# sc.net
KiCad netlist of a schematic drawn in EAGLE
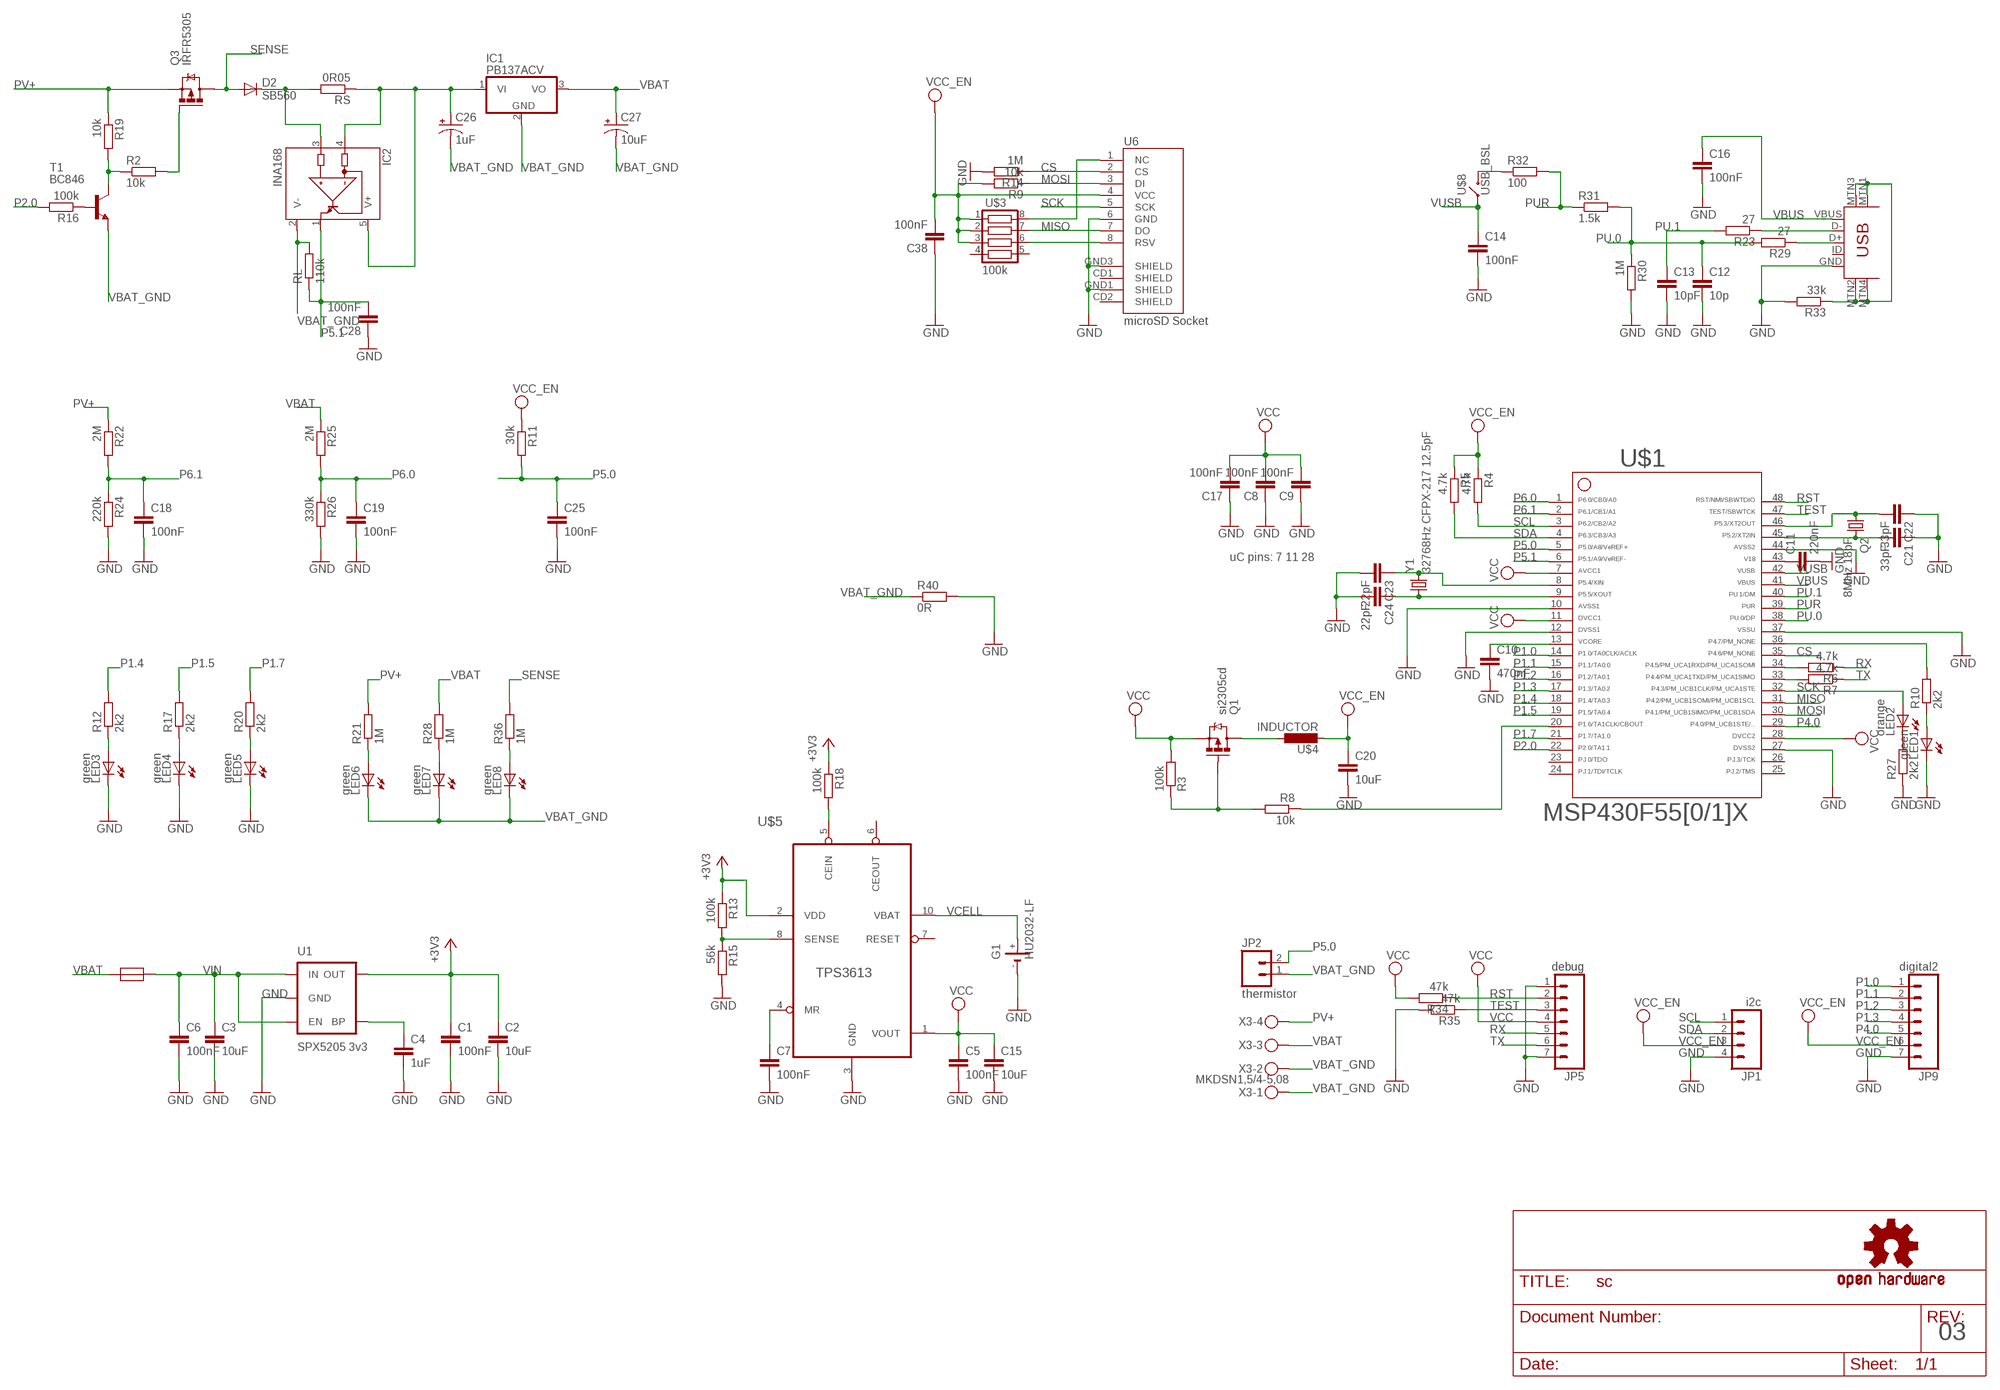
[diagram p0: schematic, sheet 1]

(export (version "E")
  (design (tool "Eeschema 10.0.6"))
  (components
    (comp (ref "C1")
      (value "100nF")
      (footprint "eagle-import:C0805")
      (libsource (lib "eagle-import") (part "C-EUC0805"))
    )
    (comp (ref "C2")
      (value "10uF")
      (footprint "eagle-import:C1206")
      (libsource (lib "eagle-import") (part "C-EUC1206"))
    )
    (comp (ref "C3")
      (value "10uF")
      (footprint "eagle-import:C1206")
      (libsource (lib "eagle-import") (part "C-EUC1206"))
    )
    (comp (ref "C4")
      (value "1uF")
      (footprint "eagle-import:C0805")
      (libsource (lib "eagle-import") (part "C-EUC0805"))
    )
    (comp (ref "C5")
      (value "100nF")
      (footprint "eagle-import:C0805")
      (libsource (lib "eagle-import") (part "C-EUC0805"))
    )
    (comp (ref "C6")
      (value "100nF")
      (footprint "eagle-import:C0805")
      (libsource (lib "eagle-import") (part "C-EUC0805"))
    )
    (comp (ref "C7")
      (value "100nF")
      (footprint "eagle-import:C0805")
      (libsource (lib "eagle-import") (part "C-EUC0805"))
    )
    (comp (ref "C8")
      (value "100nF")
      (footprint "eagle-import:C0805")
      (libsource (lib "eagle-import") (part "C-EUC0805"))
    )
    (comp (ref "C9")
      (value "100nF")
      (footprint "eagle-import:C0805")
      (libsource (lib "eagle-import") (part "C-EUC0805"))
    )
    (comp (ref "C10")
      (value "470nF")
      (footprint "eagle-import:C0805")
      (libsource (lib "eagle-import") (part "C-EUC0805"))
    )
    (comp (ref "C11")
      (value "220nF")
      (footprint "eagle-import:C0805")
      (libsource (lib "eagle-import") (part "C-EUC0805"))
    )
    (comp (ref "C12")
      (value "10p")
      (footprint "eagle-import:C0805")
      (libsource (lib "eagle-import") (part "C-EUC0805"))
    )
    (comp (ref "C13")
      (value "10pF")
      (footprint "eagle-import:C0805")
      (libsource (lib "eagle-import") (part "C-EUC0805"))
    )
    (comp (ref "C14")
      (value "100nF")
      (footprint "eagle-import:C0805")
      (libsource (lib "eagle-import") (part "C-EUC0805"))
    )
    (comp (ref "C15")
      (value "10uF")
      (footprint "eagle-import:C1206")
      (libsource (lib "eagle-import") (part "C-EUC1206"))
    )
    (comp (ref "C16")
      (value "100nF")
      (footprint "eagle-import:C0805")
      (libsource (lib "eagle-import") (part "C-EUC0805"))
    )
    (comp (ref "C17")
      (value "100nF")
      (footprint "eagle-import:C0805")
      (libsource (lib "eagle-import") (part "C-EUC0805"))
    )
    (comp (ref "C18")
      (value "100nF")
      (footprint "eagle-import:C0805")
      (libsource (lib "eagle-import") (part "C-EUC0805"))
    )
    (comp (ref "C19")
      (value "100nF")
      (footprint "eagle-import:C0805")
      (libsource (lib "eagle-import") (part "C-EUC0805"))
    )
    (comp (ref "C20")
      (value "10uF")
      (footprint "eagle-import:C1206")
      (libsource (lib "eagle-import") (part "C-EUC1206"))
    )
    (comp (ref "C21")
      (value "33pF")
      (footprint "eagle-import:C0805")
      (libsource (lib "eagle-import") (part "C-EUC0805"))
    )
    (comp (ref "C22")
      (value "33pF")
      (footprint "eagle-import:C0805")
      (libsource (lib "eagle-import") (part "C-EUC0805"))
    )
    (comp (ref "C23")
      (value "22pF")
      (footprint "eagle-import:C0805")
      (libsource (lib "eagle-import") (part "C-EUC0805"))
    )
    (comp (ref "C24")
      (value "22pF")
      (footprint "eagle-import:C0805")
      (libsource (lib "eagle-import") (part "C-EUC0805"))
    )
    (comp (ref "C25")
      (value "100nF")
      (footprint "eagle-import:C0805")
      (libsource (lib "eagle-import") (part "C-EUC0805"))
    )
    (comp (ref "C26")
      (value "1uF")
      (footprint "eagle-import:PANASONIC_D")
      (libsource (lib "eagle-import") (part "CAP_POLD"))
    )
    (comp (ref "C27")
      (value "10uF")
      (footprint "eagle-import:PANASONIC_D")
      (libsource (lib "eagle-import") (part "CAP_POLD"))
    )
    (comp (ref "C28")
      (value "100nF")
      (footprint "eagle-import:C0805")
      (libsource (lib "eagle-import") (part "C-EUC0805"))
    )
    (comp (ref "C38")
      (value "100nF")
      (footprint "eagle-import:C0805")
      (libsource (lib "eagle-import") (part "C-EUC0805"))
    )
    (comp (ref "D2")
      (value "SB560")
      (footprint "eagle-import:C1702-05")
      (libsource (lib "eagle-import") (part "DIODE-C1702-05"))
    )
    (comp (ref "G1")
      (value "HU2032-LF")
      (footprint "eagle-import:HU2032-LF")
      (libsource (lib "eagle-import") (part "HU2032-LF"))
    )
    (comp (ref "IC1")
      (value "PB137ACV")
      (footprint "eagle-import:TO220V")
      (libsource (lib "eagle-import") (part "78TV12"))
    )
    (comp (ref "IC2")
      (value "INA168")
      (footprint "eagle-import:SOT23-5")
      (fields (field (name "MF") "TEXAS INSTRUMENTS") (field (name "MPN") "INA168NA/250"))
      (libsource (lib "eagle-import") (part "INA168"))
    )
    (comp (ref "JP1")
      (value "i2c")
      (footprint "eagle-import:1X04")
      (libsource (lib "eagle-import") (part "M04PTH"))
    )
    (comp (ref "JP2")
      (value "thermistor")
      (footprint "eagle-import:1X02")
      (libsource (lib "eagle-import") (part "M02PTH"))
    )
    (comp (ref "JP5")
      (value "debug")
      (footprint "eagle-import:1X07")
      (libsource (lib "eagle-import") (part "M07"))
    )
    (comp (ref "JP9")
      (value "digital2")
      (footprint "eagle-import:1X07")
      (libsource (lib "eagle-import") (part "M07"))
    )
    (comp (ref "LED1")
      (value "green")
      (footprint "eagle-import:CHIP-LED0805")
      (libsource (lib "eagle-import") (part "LEDCHIP-LED0805"))
    )
    (comp (ref "LED2")
      (value "orange")
      (footprint "eagle-import:CHIP-LED0805")
      (libsource (lib "eagle-import") (part "LEDCHIP-LED0805"))
    )
    (comp (ref "LED3")
      (value "green")
      (footprint "eagle-import:CHIP-LED0805")
      (libsource (lib "eagle-import") (part "LEDCHIP-LED0805"))
    )
    (comp (ref "LED4")
      (value "green")
      (footprint "eagle-import:CHIP-LED0805")
      (libsource (lib "eagle-import") (part "LEDCHIP-LED0805"))
    )
    (comp (ref "LED5")
      (value "green")
      (footprint "eagle-import:CHIP-LED0805")
      (libsource (lib "eagle-import") (part "LEDCHIP-LED0805"))
    )
    (comp (ref "LED6")
      (value "green")
      (footprint "eagle-import:CHIP-LED0805")
      (libsource (lib "eagle-import") (part "LEDCHIP-LED0805"))
    )
    (comp (ref "LED7")
      (value "green")
      (footprint "eagle-import:CHIP-LED0805")
      (libsource (lib "eagle-import") (part "LEDCHIP-LED0805"))
    )
    (comp (ref "LED8")
      (value "green")
      (footprint "eagle-import:CHIP-LED0805")
      (libsource (lib "eagle-import") (part "LEDCHIP-LED0805"))
    )
    (comp (ref "Q1")
      (value "si2305cd")
      (footprint "eagle-import:SOT23-3_POWER")
      (libsource (lib "eagle-import") (part "MOSFET-PCHANNELSMD_POWER"))
    )
    (comp (ref "Q2")
      (value "8MHz 18pF")
      (footprint "eagle-import:CRYSTAL_5X3.2")
      (libsource (lib "eagle-import") (part "CRYTAL"))
    )
    (comp (ref "Q3")
      (value "IRFR5305")
      (footprint "eagle-import:D-PAK_TO252AA")
      (libsource (lib "eagle-import") (part "IRF?5305R"))
    )
    (comp (ref "R2")
      (value "10k")
      (footprint "eagle-import:R0805W")
      (libsource (lib "eagle-import") (part "R-EU_R0805W"))
    )
    (comp (ref "R3")
      (value "100k")
      (footprint "eagle-import:R0805W")
      (libsource (lib "eagle-import") (part "R-EU_R0805W"))
    )
    (comp (ref "R4")
      (value "4.7k")
      (footprint "eagle-import:R0805W")
      (libsource (lib "eagle-import") (part "R-EU_R0805W"))
    )
    (comp (ref "R5")
      (value "4.7k")
      (footprint "eagle-import:R0805W")
      (libsource (lib "eagle-import") (part "R-EU_R0805W"))
    )
    (comp (ref "R6")
      (value "4.7k")
      (footprint "eagle-import:R0805W")
      (libsource (lib "eagle-import") (part "R-EU_R0805W"))
    )
    (comp (ref "R7")
      (value "4.7k")
      (footprint "eagle-import:R0805W")
      (libsource (lib "eagle-import") (part "R-EU_R0805W"))
    )
    (comp (ref "R8")
      (value "10k")
      (footprint "eagle-import:R0805W")
      (libsource (lib "eagle-import") (part "R-EU_R0805W"))
    )
    (comp (ref "R9")
      (value "10k")
      (footprint "eagle-import:R0805W")
      (libsource (lib "eagle-import") (part "R-EU_R0805W"))
    )
    (comp (ref "R10")
      (value "2k2")
      (footprint "eagle-import:R0805W")
      (libsource (lib "eagle-import") (part "R-EU_R0805W"))
    )
    (comp (ref "R11")
      (value "30k")
      (footprint "eagle-import:R0805W")
      (libsource (lib "eagle-import") (part "R-EU_R0805W"))
    )
    (comp (ref "R12")
      (value "2k2")
      (footprint "eagle-import:R0805W")
      (libsource (lib "eagle-import") (part "R-EU_R0805W"))
    )
    (comp (ref "R13")
      (value "100k")
      (footprint "eagle-import:R0805W")
      (libsource (lib "eagle-import") (part "R-EU_R0805W"))
    )
    (comp (ref "R14")
      (value "1M")
      (footprint "eagle-import:R0805W")
      (libsource (lib "eagle-import") (part "R-EU_R0805W"))
    )
    (comp (ref "R15")
      (value "56k")
      (footprint "eagle-import:R0805W")
      (libsource (lib "eagle-import") (part "R-EU_R0805W"))
    )
    (comp (ref "R16")
      (value "100k")
      (footprint "eagle-import:R0805W")
      (libsource (lib "eagle-import") (part "R-EU_R0805W"))
    )
    (comp (ref "R17")
      (value "2k2")
      (footprint "eagle-import:R0805W")
      (libsource (lib "eagle-import") (part "R-EU_R0805W"))
    )
    (comp (ref "R18")
      (value "100k")
      (footprint "eagle-import:R0805W")
      (libsource (lib "eagle-import") (part "R-EU_R0805W"))
    )
    (comp (ref "R19")
      (value "10k")
      (footprint "eagle-import:R0805W")
      (libsource (lib "eagle-import") (part "R-EU_R0805W"))
    )
    (comp (ref "R20")
      (value "2k2")
      (footprint "eagle-import:R0805W")
      (libsource (lib "eagle-import") (part "R-EU_R0805W"))
    )
    (comp (ref "R21")
      (value "1M")
      (footprint "eagle-import:R0805W")
      (libsource (lib "eagle-import") (part "R-EU_R0805W"))
    )
    (comp (ref "R22")
      (value "2M")
      (footprint "eagle-import:R0805W")
      (libsource (lib "eagle-import") (part "R-EU_R0805W"))
    )
    (comp (ref "R23")
      (value "27")
      (footprint "eagle-import:R0805W")
      (libsource (lib "eagle-import") (part "R-EU_R0805W"))
    )
    (comp (ref "R24")
      (value "220k")
      (footprint "eagle-import:R0805W")
      (libsource (lib "eagle-import") (part "R-EU_R0805W"))
    )
    (comp (ref "R25")
      (value "2M")
      (footprint "eagle-import:R0805W")
      (libsource (lib "eagle-import") (part "R-EU_R0805W"))
    )
    (comp (ref "R26")
      (value "330k")
      (footprint "eagle-import:R0805W")
      (libsource (lib "eagle-import") (part "R-EU_R0805W"))
    )
    (comp (ref "R27")
      (value "2k2")
      (footprint "eagle-import:R0805W")
      (libsource (lib "eagle-import") (part "R-EU_R0805W"))
    )
    (comp (ref "R28")
      (value "1M")
      (footprint "eagle-import:R0805W")
      (libsource (lib "eagle-import") (part "R-EU_R0805W"))
    )
    (comp (ref "R29")
      (value "27")
      (footprint "eagle-import:R0805W")
      (libsource (lib "eagle-import") (part "R-EU_R0805W"))
    )
    (comp (ref "R30")
      (value "1M")
      (footprint "eagle-import:R0805W")
      (libsource (lib "eagle-import") (part "R-EU_R0805W"))
    )
    (comp (ref "R31")
      (value "1.5k")
      (footprint "eagle-import:R0805W")
      (libsource (lib "eagle-import") (part "R-EU_R0805W"))
    )
    (comp (ref "R32")
      (value "100")
      (footprint "eagle-import:R0805W")
      (libsource (lib "eagle-import") (part "R-EU_R0805W"))
    )
    (comp (ref "R33")
      (value "33k")
      (footprint "eagle-import:R0805W")
      (libsource (lib "eagle-import") (part "R-EU_R0805W"))
    )
    (comp (ref "R34")
      (value "47k")
      (footprint "eagle-import:R0805W")
      (libsource (lib "eagle-import") (part "R-EU_R0805W"))
    )
    (comp (ref "R35")
      (value "47k")
      (footprint "eagle-import:R0805W")
      (libsource (lib "eagle-import") (part "R-EU_R0805W"))
    )
    (comp (ref "R36")
      (value "1M")
      (footprint "eagle-import:R0805W")
      (libsource (lib "eagle-import") (part "R-EU_R0805W"))
    )
    (comp (ref "R40")
      (value "0R")
      (footprint "eagle-import:R0805W")
      (libsource (lib "eagle-import") (part "R-EU_R0805W"))
    )
    (comp (ref "RL")
      (value "110k")
      (footprint "eagle-import:R0805W")
      (libsource (lib "eagle-import") (part "R-EU_R0805W"))
    )
    (comp (ref "RS")
      (value "0R05")
      (footprint "eagle-import:TO220ACS")
      (libsource (lib "eagle-import") (part "R-EU_TO220_V"))
    )
    (comp (ref "T1")
      (value "BC846")
      (footprint "eagle-import:SOT23")
      (libsource (lib "eagle-import") (part "BC846"))
    )
    (comp (ref "U$1")
      (value "F55[0/1]X---PT48")
      (footprint "eagle-import:PT48")
      (libsource (lib "eagle-import") (part "F55[0/1]X---PT48"))
    )
    (comp (ref "U$2")
      (value "RESETTABLE")
      (footprint "eagle-import:1210")
      (libsource (lib "eagle-import") (part "RESETTABLE"))
    )
    (comp (ref "U$3")
      (value "100k")
      (footprint "eagle-import:YC164")
      (libsource (lib "eagle-import") (part "RES_ARR"))
    )
    (comp (ref "U$4")
      (value "INDUCTOR")
      (footprint "eagle-import:L0805W")
      (libsource (lib "eagle-import") (part "INDUCTOR"))
    )
    (comp (ref "U$5")
      (value "TPS3613")
      (footprint "eagle-import:MSOP_10P")
      (libsource (lib "eagle-import") (part "TPS3613"))
    )
    (comp (ref "U$6")
      (value "USB-MINIB-5PIN")
      (footprint "eagle-import:USB-MINIB")
      (libsource (lib "eagle-import") (part "USB-MINIB-5PIN"))
    )
    (comp (ref "U$7")
      (value "OSHW-LOGOM")
      (footprint "eagle-import:OSHW-LOGO-M")
      (libsource (lib "eagle-import") (part "OSHW-LOGOM"))
    )
    (comp (ref "U$8")
      (value "USB_BSL")
      (footprint "eagle-import:6X3.5_TACTILE_SW")
      (libsource (lib "eagle-import") (part "TACT_SW"))
    )
    (comp (ref "U1")
      (value "SPX5205 3v3")
      (footprint "eagle-import:SOT23-5")
      (libsource (lib "eagle-import") (part "V_REG_LDOSMD"))
    )
    (comp (ref "U6")
      (value "microSD Socket")
      (footprint "eagle-import:MICRO-SD-SOCKET-PP")
      (libsource (lib "eagle-import") (part "USD-SOCKETNEW"))
    )
    (comp (ref "X3")
      (value "MKDSN1,5/4-5,08")
      (footprint "eagle-import:MKDSN1,5_4-5,08")
      (fields (field (name "MPN") "SMKDSN1,5/4-5,08"))
      (libsource (lib "eagle-import") (part "MKDSN1,5/4-5,08"))
    )
    (comp (ref "Y1")
      (value "32768Hz CFPX-217 12.5pF")
      (footprint "eagle-import:CRYSTAL-SMD-3.2X1.5")
      (libsource (lib "eagle-import") (part "CRYSTAL3.2X1.5"))
    )
  )
  (nets
    (net (code "1") (name "+3V3") (class "Default")
      (node (ref "C1") (pin "1") (pinfunction "1_1") (pintype "passive"))
      (node (ref "C2") (pin "1") (pinfunction "1_1") (pintype "passive"))
      (node (ref "R13") (pin "1") (pinfunction "1_1") (pintype "passive"))
      (node (ref "R18") (pin "1") (pinfunction "1_1") (pintype "passive"))
      (node (ref "U$5") (pin "2") (pinfunction "VDD_2") (pintype "power_in"))
      (node (ref "U1") (pin "5") (pinfunction "OUT_5") (pintype "passive"))
    )
    (net (code "2") (name "/CS") (class "Default")
      (node (ref "R14") (pin "1") (pinfunction "1_1") (pintype "passive"))
      (node (ref "U$1") (pin "35") (pinfunction "35_35") (pintype "bidirectional"))
      (node (ref "U6") (pin "2") (pinfunction "CS_2") (pintype "bidirectional"))
    )
    (net (code "3") (name "/MISO") (class "Default")
      (node (ref "U$1") (pin "31") (pinfunction "31_31") (pintype "bidirectional"))
      (node (ref "U$3") (pin "7") (pinfunction "7_7") (pintype "passive"))
      (node (ref "U6") (pin "7") (pinfunction "DO_7") (pintype "bidirectional"))
    )
    (net (code "4") (name "/MOSI") (class "Default")
      (node (ref "R9") (pin "1") (pinfunction "1_1") (pintype "passive"))
      (node (ref "U$1") (pin "30") (pinfunction "30_30") (pintype "bidirectional"))
      (node (ref "U6") (pin "3") (pinfunction "DI_3") (pintype "bidirectional"))
    )
    (net (code "5") (name "/P1.0") (class "Default")
      (node (ref "JP9") (pin "1") (pinfunction "1_1") (pintype "passive"))
      (node (ref "U$1") (pin "14") (pinfunction "14_14") (pintype "bidirectional"))
    )
    (net (code "6") (name "/P1.1") (class "Default")
      (node (ref "JP9") (pin "2") (pinfunction "2_2") (pintype "passive"))
      (node (ref "U$1") (pin "15") (pinfunction "15_15") (pintype "bidirectional"))
    )
    (net (code "7") (name "/P1.2") (class "Default")
      (node (ref "JP9") (pin "3") (pinfunction "3_3") (pintype "passive"))
      (node (ref "U$1") (pin "16") (pinfunction "16_16") (pintype "bidirectional"))
    )
    (net (code "8") (name "/P1.3") (class "Default")
      (node (ref "JP9") (pin "4") (pinfunction "4_4") (pintype "passive"))
      (node (ref "U$1") (pin "17") (pinfunction "17_17") (pintype "bidirectional"))
    )
    (net (code "9") (name "/P1.4") (class "Default")
      (node (ref "R12") (pin "2") (pinfunction "2_2") (pintype "passive"))
      (node (ref "U$1") (pin "18") (pinfunction "18_18") (pintype "bidirectional"))
    )
    (net (code "10") (name "/P1.5") (class "Default")
      (node (ref "R17") (pin "2") (pinfunction "2_2") (pintype "passive"))
      (node (ref "U$1") (pin "19") (pinfunction "19_19") (pintype "bidirectional"))
    )
    (net (code "11") (name "/P1.7") (class "Default")
      (node (ref "R20") (pin "2") (pinfunction "2_2") (pintype "passive"))
      (node (ref "U$1") (pin "21") (pinfunction "21_21") (pintype "bidirectional"))
    )
    (net (code "12") (name "/P2.0") (class "Default")
      (node (ref "R16") (pin "2") (pinfunction "2_2") (pintype "passive"))
      (node (ref "U$1") (pin "22") (pinfunction "22_22") (pintype "bidirectional"))
    )
    (net (code "13") (name "/P4.0") (class "Default")
      (node (ref "JP9") (pin "5") (pinfunction "5_5") (pintype "passive"))
      (node (ref "U$1") (pin "29") (pinfunction "29_29") (pintype "bidirectional"))
    )
    (net (code "14") (name "/P5.0") (class "Default")
      (node (ref "C25") (pin "1") (pinfunction "1_1") (pintype "passive"))
      (node (ref "JP2") (pin "2") (pinfunction "2_2") (pintype "passive"))
      (node (ref "R11") (pin "2") (pinfunction "2_2") (pintype "passive"))
      (node (ref "U$1") (pin "5") (pinfunction "5_5") (pintype "bidirectional"))
    )
    (net (code "15") (name "/P5.1") (class "Default")
      (node (ref "C28") (pin "2") (pinfunction "2_2") (pintype "passive"))
      (node (ref "IC2") (pin "1") (pinfunction "OUT_1") (pintype "output"))
      (node (ref "RL") (pin "1") (pinfunction "1_1") (pintype "passive"))
      (node (ref "U$1") (pin "6") (pinfunction "6_6") (pintype "bidirectional"))
    )
    (net (code "16") (name "/P6.0") (class "Default")
      (node (ref "C19") (pin "1") (pinfunction "1_1") (pintype "passive"))
      (node (ref "R25") (pin "2") (pinfunction "2_2") (pintype "passive"))
      (node (ref "R26") (pin "1") (pinfunction "1_1") (pintype "passive"))
      (node (ref "U$1") (pin "1") (pinfunction "1_1") (pintype "bidirectional"))
    )
    (net (code "17") (name "/P6.1") (class "Default")
      (node (ref "C18") (pin "1") (pinfunction "1_1") (pintype "passive"))
      (node (ref "R22") (pin "2") (pinfunction "2_2") (pintype "passive"))
      (node (ref "R24") (pin "1") (pinfunction "1_1") (pintype "passive"))
      (node (ref "U$1") (pin "2") (pinfunction "2_2") (pintype "bidirectional"))
    )
    (net (code "18") (name "/PU.0") (class "Default")
      (node (ref "C12") (pin "1") (pinfunction "1_1") (pintype "passive"))
      (node (ref "R29") (pin "2") (pinfunction "2_2") (pintype "passive"))
      (node (ref "R30") (pin "1") (pinfunction "1_1") (pintype "passive"))
      (node (ref "R31") (pin "2") (pinfunction "2_2") (pintype "passive"))
      (node (ref "U$1") (pin "38") (pinfunction "38_38") (pintype "bidirectional"))
    )
    (net (code "19") (name "/PU.1") (class "Default")
      (node (ref "C13") (pin "1") (pinfunction "1_1") (pintype "passive"))
      (node (ref "R23") (pin "2") (pinfunction "2_2") (pintype "passive"))
      (node (ref "U$1") (pin "40") (pinfunction "40_40") (pintype "bidirectional"))
    )
    (net (code "20") (name "/PUR") (class "Default")
      (node (ref "R31") (pin "1") (pinfunction "1_1") (pintype "passive"))
      (node (ref "R32") (pin "2") (pinfunction "2_2") (pintype "passive"))
      (node (ref "U$1") (pin "39") (pinfunction "39_39") (pintype "bidirectional"))
    )
    (net (code "21") (name "/PV+") (class "Default")
      (node (ref "Q3") (pin "3") (pinfunction "S_3") (pintype "passive"))
      (node (ref "R19") (pin "1") (pinfunction "1_1") (pintype "passive"))
      (node (ref "R21") (pin "2") (pinfunction "2_2") (pintype "passive"))
      (node (ref "R22") (pin "1") (pinfunction "1_1") (pintype "passive"))
      (node (ref "X3") (pin "4") (pinfunction "KL_4") (pintype "passive"))
    )
    (net (code "22") (name "/RST") (class "Default")
      (node (ref "JP5") (pin "2") (pinfunction "2_2") (pintype "passive"))
      (node (ref "R34") (pin "1") (pinfunction "1_1") (pintype "passive"))
      (node (ref "U$1") (pin "48") (pinfunction "48_48") (pintype "bidirectional"))
    )
    (net (code "23") (name "/RX") (class "Default")
      (node (ref "JP5") (pin "5") (pinfunction "5_5") (pintype "passive"))
      (node (ref "R6") (pin "1") (pinfunction "1_1") (pintype "passive"))
    )
    (net (code "24") (name "/SCK") (class "Default")
      (node (ref "LED2") (pin "A") (pinfunction "A_A") (pintype "passive"))
      (node (ref "U$1") (pin "32") (pinfunction "32_32") (pintype "bidirectional"))
      (node (ref "U6") (pin "5") (pinfunction "SCK_5") (pintype "bidirectional"))
    )
    (net (code "25") (name "/SCL") (class "Default")
      (node (ref "JP1") (pin "1") (pinfunction "1_1") (pintype "passive"))
      (node (ref "R4") (pin "2") (pinfunction "2_2") (pintype "passive"))
      (node (ref "U$1") (pin "3") (pinfunction "3_3") (pintype "bidirectional"))
    )
    (net (code "26") (name "/SDA") (class "Default")
      (node (ref "JP1") (pin "2") (pinfunction "2_2") (pintype "passive"))
      (node (ref "R5") (pin "2") (pinfunction "2_2") (pintype "passive"))
      (node (ref "U$1") (pin "4") (pinfunction "4_4") (pintype "bidirectional"))
    )
    (net (code "27") (name "/SENSE") (class "Default")
      (node (ref "D2") (pin "A") (pinfunction "A_A") (pintype "passive"))
      (node (ref "Q3") (pin "4") (pinfunction "D_4") (pintype "passive"))
      (node (ref "R36") (pin "2") (pinfunction "2_2") (pintype "passive"))
    )
    (net (code "28") (name "/TEST") (class "Default")
      (node (ref "JP5") (pin "3") (pinfunction "3_3") (pintype "passive"))
      (node (ref "R35") (pin "1") (pinfunction "1_1") (pintype "passive"))
      (node (ref "U$1") (pin "47") (pinfunction "47_47") (pintype "input"))
    )
    (net (code "29") (name "/TX") (class "Default")
      (node (ref "JP5") (pin "6") (pinfunction "6_6") (pintype "passive"))
      (node (ref "R7") (pin "1") (pinfunction "1_1") (pintype "passive"))
    )
    (net (code "30") (name "/VBAT") (class "Default")
      (node (ref "C27") (pin "+") (pinfunction "+_+") (pintype "passive"))
      (node (ref "IC1") (pin "3") (pinfunction "VO_3") (pintype "passive"))
      (node (ref "R25") (pin "1") (pinfunction "1_1") (pintype "passive"))
      (node (ref "R28") (pin "2") (pinfunction "2_2") (pintype "passive"))
      (node (ref "U$2") (pin "P$1") (pinfunction "P$1_P$1") (pintype "bidirectional"))
      (node (ref "X3") (pin "3") (pinfunction "KL_3") (pintype "passive"))
    )
    (net (code "31") (name "/VBAT_GND") (class "Default")
      (node (ref "C26") (pin "-") (pinfunction "-_-") (pintype "passive"))
      (node (ref "C27") (pin "-") (pinfunction "-_-") (pintype "passive"))
      (node (ref "IC1") (pin "2") (pinfunction "GND_2") (pintype "passive"))
      (node (ref "IC2") (pin "2") (pinfunction "V-_2") (pintype "power_in"))
      (node (ref "JP2") (pin "1") (pinfunction "1_1") (pintype "passive"))
      (node (ref "LED6") (pin "C") (pinfunction "C_C") (pintype "passive"))
      (node (ref "LED7") (pin "C") (pinfunction "C_C") (pintype "passive"))
      (node (ref "LED8") (pin "C") (pinfunction "C_C") (pintype "passive"))
      (node (ref "R40") (pin "1") (pinfunction "1_1") (pintype "passive"))
      (node (ref "RL") (pin "2") (pinfunction "2_2") (pintype "passive"))
      (node (ref "T1") (pin "2") (pinfunction "E_2") (pintype "passive"))
      (node (ref "X3") (pin "1") (pinfunction "KL_1") (pintype "passive"))
      (node (ref "X3") (pin "2") (pinfunction "KL_2") (pintype "passive"))
    )
    (net (code "32") (name "/VBUS") (class "Default")
      (node (ref "C16") (pin "1") (pinfunction "1_1") (pintype "passive"))
      (node (ref "U$1") (pin "41") (pinfunction "41_41") (pintype "power_in"))
      (node (ref "U$6") (pin "VBUS") (pinfunction "VBUS_VBUS") (pintype "bidirectional"))
    )
    (net (code "33") (name "/VCELL") (class "Default")
      (node (ref "G1") (pin "+") (pinfunction "+_+") (pintype "passive"))
      (node (ref "U$5") (pin "10") (pinfunction "VBAT_10") (pintype "power_in"))
    )
    (net (code "34") (name "/VIN") (class "Default")
      (node (ref "C3") (pin "1") (pinfunction "1_1") (pintype "passive"))
      (node (ref "C6") (pin "1") (pinfunction "1_1") (pintype "passive"))
      (node (ref "U$2") (pin "P$2") (pinfunction "P$2_P$2") (pintype "bidirectional"))
      (node (ref "U1") (pin "1") (pinfunction "IN_1") (pintype "input"))
      (node (ref "U1") (pin "3") (pinfunction "EN_3") (pintype "input"))
    )
    (net (code "35") (name "/VUSB") (class "Default")
      (node (ref "C14") (pin "1") (pinfunction "1_1") (pintype "passive"))
      (node (ref "U$1") (pin "42") (pinfunction "42_42") (pintype "power_in"))
      (node (ref "U$8") (pin "1") (pinfunction "1_1") (pintype "passive"))
    )
    (net (code "36") (name "GND") (class "Default")
      (node (ref "C1") (pin "2") (pinfunction "2_2") (pintype "passive"))
      (node (ref "C10") (pin "2") (pinfunction "2_2") (pintype "passive"))
      (node (ref "C11") (pin "2") (pinfunction "2_2") (pintype "passive"))
      (node (ref "C12") (pin "2") (pinfunction "2_2") (pintype "passive"))
      (node (ref "C13") (pin "2") (pinfunction "2_2") (pintype "passive"))
      (node (ref "C14") (pin "2") (pinfunction "2_2") (pintype "passive"))
      (node (ref "C15") (pin "2") (pinfunction "2_2") (pintype "passive"))
      (node (ref "C16") (pin "2") (pinfunction "2_2") (pintype "passive"))
      (node (ref "C17") (pin "1") (pinfunction "1_1") (pintype "passive"))
      (node (ref "C18") (pin "2") (pinfunction "2_2") (pintype "passive"))
      (node (ref "C19") (pin "2") (pinfunction "2_2") (pintype "passive"))
      (node (ref "C2") (pin "2") (pinfunction "2_2") (pintype "passive"))
      (node (ref "C20") (pin "2") (pinfunction "2_2") (pintype "passive"))
      (node (ref "C21") (pin "1") (pinfunction "1_1") (pintype "passive"))
      (node (ref "C22") (pin "1") (pinfunction "1_1") (pintype "passive"))
      (node (ref "C23") (pin "2") (pinfunction "2_2") (pintype "passive"))
      (node (ref "C24") (pin "2") (pinfunction "2_2") (pintype "passive"))
      (node (ref "C25") (pin "2") (pinfunction "2_2") (pintype "passive"))
      (node (ref "C28") (pin "1") (pinfunction "1_1") (pintype "passive"))
      (node (ref "C3") (pin "2") (pinfunction "2_2") (pintype "passive"))
      (node (ref "C38") (pin "1") (pinfunction "1_1") (pintype "passive"))
      (node (ref "C4") (pin "2") (pinfunction "2_2") (pintype "passive"))
      (node (ref "C5") (pin "2") (pinfunction "2_2") (pintype "passive"))
      (node (ref "C6") (pin "2") (pinfunction "2_2") (pintype "passive"))
      (node (ref "C7") (pin "2") (pinfunction "2_2") (pintype "passive"))
      (node (ref "C8") (pin "1") (pinfunction "1_1") (pintype "passive"))
      (node (ref "C9") (pin "1") (pinfunction "1_1") (pintype "passive"))
      (node (ref "G1") (pin "-") (pinfunction "-_-") (pintype "passive"))
      (node (ref "JP1") (pin "4") (pinfunction "4_4") (pintype "passive"))
      (node (ref "JP5") (pin "1") (pinfunction "1_1") (pintype "passive"))
      (node (ref "JP5") (pin "7") (pinfunction "7_7") (pintype "passive"))
      (node (ref "JP9") (pin "7") (pinfunction "7_7") (pintype "passive"))
      (node (ref "LED1") (pin "C") (pinfunction "C_C") (pintype "passive"))
      (node (ref "LED3") (pin "C") (pinfunction "C_C") (pintype "passive"))
      (node (ref "LED4") (pin "C") (pinfunction "C_C") (pintype "passive"))
      (node (ref "LED5") (pin "C") (pinfunction "C_C") (pintype "passive"))
      (node (ref "R14") (pin "2") (pinfunction "2_2") (pintype "passive"))
      (node (ref "R15") (pin "2") (pinfunction "2_2") (pintype "passive"))
      (node (ref "R24") (pin "2") (pinfunction "2_2") (pintype "passive"))
      (node (ref "R26") (pin "2") (pinfunction "2_2") (pintype "passive"))
      (node (ref "R27") (pin "1") (pinfunction "1_1") (pintype "passive"))
      (node (ref "R30") (pin "2") (pinfunction "2_2") (pintype "passive"))
      (node (ref "R33") (pin "2") (pinfunction "2_2") (pintype "passive"))
      (node (ref "R35") (pin "2") (pinfunction "2_2") (pintype "passive"))
      (node (ref "R40") (pin "2") (pinfunction "2_2") (pintype "passive"))
      (node (ref "U$1") (pin "10") (pinfunction "10_10") (pintype "power_in"))
      (node (ref "U$1") (pin "12") (pinfunction "12_12") (pintype "power_in"))
      (node (ref "U$1") (pin "27") (pinfunction "27_27") (pintype "power_in"))
      (node (ref "U$1") (pin "37") (pinfunction "37_37") (pintype "power_in"))
      (node (ref "U$1") (pin "44") (pinfunction "44_44") (pintype "power_in"))
      (node (ref "U$5") (pin "3") (pinfunction "GND_3") (pintype "passive"))
      (node (ref "U$6") (pin "GND") (pinfunction "GND_GND") (pintype "bidirectional"))
      (node (ref "U1") (pin "2") (pinfunction "GND_2") (pintype "input"))
      (node (ref "U6") (pin "6") (pinfunction "GND_6") (pintype "bidirectional"))
      (node (ref "U6") (pin "GND1") (pinfunction "SHIELD_GND1") (pintype "bidirectional"))
      (node (ref "U6") (pin "GND3") (pinfunction "SHIELD_GND3") (pintype "bidirectional"))
    )
    (net (code "37") (name "Net-(C10-Pad1)") (class "Default")
      (node (ref "C10") (pin "1") (pinfunction "1_1") (pintype "passive"))
      (node (ref "U$1") (pin "13") (pinfunction "13_13") (pintype "power_in"))
    )
    (net (code "38") (name "Net-(C11-Pad1)") (class "Default")
      (node (ref "C11") (pin "1") (pinfunction "1_1") (pintype "passive"))
      (node (ref "U$1") (pin "43") (pinfunction "43_43") (pintype "power_in"))
    )
    (net (code "39") (name "Net-(IC1-VI)") (class "Default")
      (node (ref "C26") (pin "+") (pinfunction "+_+") (pintype "passive"))
      (node (ref "IC1") (pin "1") (pinfunction "VI_1") (pintype "input"))
      (node (ref "IC2") (pin "4") (pinfunction "IN-_4") (pintype "input"))
      (node (ref "IC2") (pin "5") (pinfunction "V+_5") (pintype "power_in"))
      (node (ref "RS") (pin "A") (pinfunction "1_A") (pintype "passive"))
    )
    (net (code "40") (name "Net-(IC2-IN+)") (class "Default")
      (node (ref "D2") (pin "C") (pinfunction "C_C") (pintype "passive"))
      (node (ref "IC2") (pin "3") (pinfunction "IN+_3") (pintype "input"))
      (node (ref "RS") (pin "C") (pinfunction "2_C") (pintype "passive"))
    )
    (net (code "41") (name "Net-(LED1-PadA)") (class "Default")
      (node (ref "LED1") (pin "A") (pinfunction "A_A") (pintype "passive"))
      (node (ref "R10") (pin "1") (pinfunction "1_1") (pintype "passive"))
    )
    (net (code "42") (name "Net-(LED2-PadC)") (class "Default")
      (node (ref "LED2") (pin "C") (pinfunction "C_C") (pintype "passive"))
      (node (ref "R27") (pin "2") (pinfunction "2_2") (pintype "passive"))
    )
    (net (code "43") (name "Net-(LED3-PadA)") (class "Default")
      (node (ref "LED3") (pin "A") (pinfunction "A_A") (pintype "passive"))
      (node (ref "R12") (pin "1") (pinfunction "1_1") (pintype "passive"))
    )
    (net (code "44") (name "Net-(LED4-PadA)") (class "Default")
      (node (ref "LED4") (pin "A") (pinfunction "A_A") (pintype "passive"))
      (node (ref "R17") (pin "1") (pinfunction "1_1") (pintype "passive"))
    )
    (net (code "45") (name "Net-(LED5-PadA)") (class "Default")
      (node (ref "LED5") (pin "A") (pinfunction "A_A") (pintype "passive"))
      (node (ref "R20") (pin "1") (pinfunction "1_1") (pintype "passive"))
    )
    (net (code "46") (name "Net-(LED6-PadA)") (class "Default")
      (node (ref "LED6") (pin "A") (pinfunction "A_A") (pintype "passive"))
      (node (ref "R21") (pin "1") (pinfunction "1_1") (pintype "passive"))
    )
    (net (code "47") (name "Net-(LED7-PadA)") (class "Default")
      (node (ref "LED7") (pin "A") (pinfunction "A_A") (pintype "passive"))
      (node (ref "R28") (pin "1") (pinfunction "1_1") (pintype "passive"))
    )
    (net (code "48") (name "Net-(LED8-PadA)") (class "Default")
      (node (ref "LED8") (pin "A") (pinfunction "A_A") (pintype "passive"))
      (node (ref "R36") (pin "1") (pinfunction "1_1") (pintype "passive"))
    )
    (net (code "49") (name "Net-(Q1-D)") (class "Default")
      (node (ref "Q1") (pin "3") (pinfunction "D_3") (pintype "passive"))
      (node (ref "U$4") (pin "1") (pinfunction "1_1") (pintype "passive"))
    )
    (net (code "50") (name "Net-(Q1-G)") (class "Default")
      (node (ref "Q1") (pin "1") (pinfunction "G_1") (pintype "passive"))
      (node (ref "R3") (pin "1") (pinfunction "1_1") (pintype "passive"))
      (node (ref "R8") (pin "2") (pinfunction "2_2") (pintype "passive"))
    )
    (net (code "51") (name "Net-(Q2-1)") (class "Default")
      (node (ref "C22") (pin "2") (pinfunction "2_2") (pintype "passive"))
      (node (ref "Q2") (pin "P$1") (pinfunction "1_P$1") (pintype "passive"))
      (node (ref "U$1") (pin "46") (pinfunction "46_46") (pintype "power_in"))
    )
    (net (code "52") (name "Net-(Q2-2)") (class "Default")
      (node (ref "C21") (pin "2") (pinfunction "2_2") (pintype "passive"))
      (node (ref "Q2") (pin "P$2") (pinfunction "2_P$2") (pintype "passive"))
      (node (ref "U$1") (pin "45") (pinfunction "45_45") (pintype "bidirectional"))
    )
    (net (code "53") (name "Net-(Q3-G)") (class "Default")
      (node (ref "Q3") (pin "1") (pinfunction "G_1") (pintype "passive"))
      (node (ref "R2") (pin "2") (pinfunction "2_2") (pintype "passive"))
    )
    (net (code "54") (name "Net-(R6-Pad2)") (class "Default")
      (node (ref "R6") (pin "2") (pinfunction "2_2") (pintype "passive"))
      (node (ref "U$1") (pin "34") (pinfunction "34_34") (pintype "bidirectional"))
    )
    (net (code "55") (name "Net-(R7-Pad2)") (class "Default")
      (node (ref "R7") (pin "2") (pinfunction "2_2") (pintype "passive"))
      (node (ref "U$1") (pin "33") (pinfunction "33_33") (pintype "bidirectional"))
    )
    (net (code "56") (name "Net-(R8-Pad1)") (class "Default")
      (node (ref "R8") (pin "1") (pinfunction "1_1") (pintype "passive"))
      (node (ref "U$1") (pin "20") (pinfunction "20_20") (pintype "bidirectional"))
    )
    (net (code "57") (name "Net-(R10-Pad2)") (class "Default")
      (node (ref "R10") (pin "2") (pinfunction "2_2") (pintype "passive"))
      (node (ref "U$1") (pin "36") (pinfunction "36_36") (pintype "bidirectional"))
    )
    (net (code "58") (name "Net-(R23-Pad1)") (class "Default")
      (node (ref "R23") (pin "1") (pinfunction "1_1") (pintype "passive"))
      (node (ref "U$6") (pin "D-") (pinfunction "D-_D-") (pintype "bidirectional"))
    )
    (net (code "59") (name "Net-(R29-Pad1)") (class "Default")
      (node (ref "R29") (pin "1") (pinfunction "1_1") (pintype "passive"))
      (node (ref "U$6") (pin "D+") (pinfunction "D+_D+") (pintype "bidirectional"))
    )
    (net (code "60") (name "Net-(R32-Pad1)") (class "Default")
      (node (ref "R32") (pin "1") (pinfunction "1_1") (pintype "passive"))
      (node (ref "U$8") (pin "2") (pinfunction "2_2") (pintype "passive"))
    )
    (net (code "61") (name "Net-(T1-B)") (class "Default")
      (node (ref "R16") (pin "1") (pinfunction "1_1") (pintype "passive"))
      (node (ref "T1") (pin "1") (pinfunction "B_1") (pintype "passive"))
    )
    (net (code "62") (name "Net-(T1-C)") (class "Default")
      (node (ref "R19") (pin "2") (pinfunction "2_2") (pintype "passive"))
      (node (ref "R2") (pin "1") (pinfunction "1_1") (pintype "passive"))
      (node (ref "T1") (pin "3") (pinfunction "C_3") (pintype "passive"))
    )
    (net (code "63") (name "Net-(U$5-CEIN)") (class "Default")
      (node (ref "R18") (pin "2") (pinfunction "2_2") (pintype "passive"))
      (node (ref "U$5") (pin "5") (pinfunction "CEIN_5") (pintype "input"))
    )
    (net (code "64") (name "Net-(U$5-MR)") (class "Default")
      (node (ref "C7") (pin "1") (pinfunction "1_1") (pintype "passive"))
      (node (ref "U$5") (pin "4") (pinfunction "MR_4") (pintype "input"))
    )
    (net (code "65") (name "Net-(U$5-SENSE)") (class "Default")
      (node (ref "R13") (pin "2") (pinfunction "2_2") (pintype "passive"))
      (node (ref "R15") (pin "1") (pinfunction "1_1") (pintype "passive"))
      (node (ref "U$5") (pin "8") (pinfunction "SENSE_8") (pintype "input"))
    )
    (net (code "66") (name "Net-(U$6-MTN1)") (class "Default")
      (node (ref "R33") (pin "1") (pinfunction "1_1") (pintype "passive"))
      (node (ref "U$6") (pin "MTN1") (pinfunction "MTN2_MTN1") (pintype "bidirectional"))
      (node (ref "U$6") (pin "MTN2") (pinfunction "MTN3_MTN2") (pintype "bidirectional"))
      (node (ref "U$6") (pin "MTN3") (pinfunction "MTN1_MTN3") (pintype "bidirectional"))
      (node (ref "U$6") (pin "MTN4") (pinfunction "MTN4_MTN4") (pintype "bidirectional"))
    )
    (net (code "67") (name "Net-(U1-BP)") (class "Default")
      (node (ref "C4") (pin "1") (pinfunction "1_1") (pintype "passive"))
      (node (ref "U1") (pin "4") (pinfunction "BP_4") (pintype "input"))
    )
    (net (code "68") (name "Net-(U6-NC)") (class "Default")
      (node (ref "U$3") (pin "8") (pinfunction "8_8") (pintype "passive"))
      (node (ref "U6") (pin "1") (pinfunction "NC_1") (pintype "bidirectional"))
    )
    (net (code "69") (name "Net-(U6-RSV)") (class "Default")
      (node (ref "U$3") (pin "6") (pinfunction "6_6") (pintype "passive"))
      (node (ref "U6") (pin "8") (pinfunction "RSV_8") (pintype "bidirectional"))
    )
    (net (code "70") (name "Net-(Y1-1)") (class "Default")
      (node (ref "C24") (pin "1") (pinfunction "1_1") (pintype "passive"))
      (node (ref "U$1") (pin "9") (pinfunction "9_9") (pintype "bidirectional"))
      (node (ref "Y1") (pin "P$1") (pinfunction "1_P$1") (pintype "passive"))
    )
    (net (code "71") (name "Net-(Y1-2)") (class "Default")
      (node (ref "C23") (pin "1") (pinfunction "1_1") (pintype "passive"))
      (node (ref "U$1") (pin "8") (pinfunction "8_8") (pintype "bidirectional"))
      (node (ref "Y1") (pin "P$2") (pinfunction "2_P$2") (pintype "passive"))
    )
    (net (code "72") (name "VCC") (class "Default")
      (node (ref "C15") (pin "1") (pinfunction "1_1") (pintype "passive"))
      (node (ref "C17") (pin "2") (pinfunction "2_2") (pintype "passive"))
      (node (ref "C5") (pin "1") (pinfunction "1_1") (pintype "passive"))
      (node (ref "C8") (pin "2") (pinfunction "2_2") (pintype "passive"))
      (node (ref "C9") (pin "2") (pinfunction "2_2") (pintype "passive"))
      (node (ref "JP5") (pin "4") (pinfunction "4_4") (pintype "passive"))
      (node (ref "Q1") (pin "2") (pinfunction "S_2") (pintype "passive"))
      (node (ref "R3") (pin "2") (pinfunction "2_2") (pintype "passive"))
      (node (ref "R34") (pin "2") (pinfunction "2_2") (pintype "passive"))
      (node (ref "U$1") (pin "11") (pinfunction "11_11") (pintype "power_in"))
      (node (ref "U$1") (pin "28") (pinfunction "28_28") (pintype "power_in"))
      (node (ref "U$1") (pin "7") (pinfunction "7_7") (pintype "power_in"))
      (node (ref "U$5") (pin "1") (pinfunction "VOUT_1") (pintype "power_in"))
    )
    (net (code "73") (name "VCC_EN") (class "Default")
      (node (ref "C20") (pin "1") (pinfunction "1_1") (pintype "passive"))
      (node (ref "C38") (pin "2") (pinfunction "2_2") (pintype "passive"))
      (node (ref "JP1") (pin "3") (pinfunction "3_3") (pintype "passive"))
      (node (ref "JP9") (pin "6") (pinfunction "6_6") (pintype "passive"))
      (node (ref "R11") (pin "1") (pinfunction "1_1") (pintype "passive"))
      (node (ref "R4") (pin "1") (pinfunction "1_1") (pintype "passive"))
      (node (ref "R5") (pin "1") (pinfunction "1_1") (pintype "passive"))
      (node (ref "R9") (pin "2") (pinfunction "2_2") (pintype "passive"))
      (node (ref "U$3") (pin "1") (pinfunction "1_1") (pintype "passive"))
      (node (ref "U$3") (pin "2") (pinfunction "2_2") (pintype "passive"))
      (node (ref "U$3") (pin "3") (pinfunction "3_3") (pintype "passive"))
      (node (ref "U$4") (pin "2") (pinfunction "2_2") (pintype "passive"))
      (node (ref "U6") (pin "4") (pinfunction "VCC_4") (pintype "bidirectional"))
    )
    (net (code "74") (name "unconnected-(G1-+-Pad+@1)") (class "Default")
      (node (ref "G1") (pin "+@1") (pinfunction "+_+@1") (pintype "passive"))
    )
    (net (code "75") (name "unconnected-(U$1-Pad23)") (class "Default")
      (node (ref "U$1") (pin "23") (pinfunction "23_23") (pintype "bidirectional"))
    )
    (net (code "76") (name "unconnected-(U$1-Pad24)") (class "Default")
      (node (ref "U$1") (pin "24") (pinfunction "24_24") (pintype "bidirectional"))
    )
    (net (code "77") (name "unconnected-(U$1-Pad25)") (class "Default")
      (node (ref "U$1") (pin "25") (pinfunction "25_25") (pintype "bidirectional"))
    )
    (net (code "78") (name "unconnected-(U$1-Pad26)") (class "Default")
      (node (ref "U$1") (pin "26") (pinfunction "26_26") (pintype "bidirectional"))
    )
    (net (code "79") (name "unconnected-(U$3-Pad4)") (class "Default")
      (node (ref "U$3") (pin "4") (pinfunction "4_4") (pintype "passive"))
    )
    (net (code "80") (name "unconnected-(U$3-Pad5)") (class "Default")
      (node (ref "U$3") (pin "5") (pinfunction "5_5") (pintype "passive"))
    )
    (net (code "81") (name "unconnected-(U$5-CEOUT-Pad6)") (class "Default")
      (node (ref "U$5") (pin "6") (pinfunction "CEOUT_6") (pintype "output"))
    )
    (net (code "82") (name "unconnected-(U$5-RESET-Pad7)") (class "Default")
      (node (ref "U$5") (pin "7") (pinfunction "RESET_7") (pintype "output"))
    )
    (net (code "83") (name "unconnected-(U$6-PadID)") (class "Default")
      (node (ref "U$6") (pin "ID") (pinfunction "ID_ID") (pintype "bidirectional"))
    )
    (net (code "84") (name "unconnected-(U6-SHIELD-PadCD1)") (class "Default")
      (node (ref "U6") (pin "CD1") (pinfunction "SHIELD_CD1") (pintype "bidirectional"))
    )
    (net (code "85") (name "unconnected-(U6-SHIELD-PadCD2)") (class "Default")
      (node (ref "U6") (pin "CD2") (pinfunction "SHIELD_CD2") (pintype "bidirectional"))
    )
  )
)
